# REVB.net
KiCad netlist of a schematic drawn in EAGLE
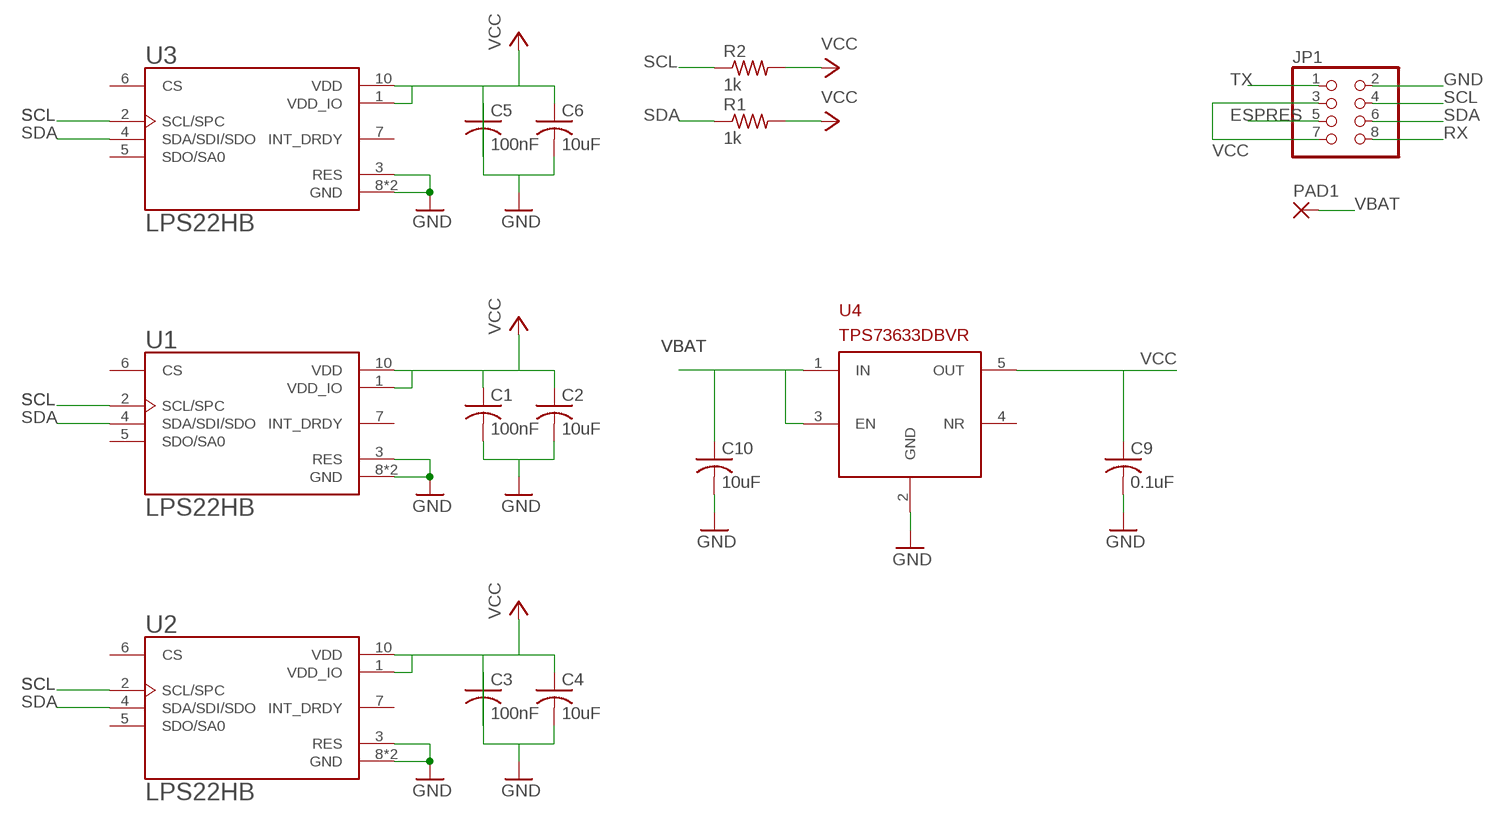
[diagram p0: schematic, sheet 1]

(export (version "E")
  (design (tool "Eeschema 10.0.6"))
  (components
    (comp (ref "C1")
      (value "100nF")
      (footprint "eagle-import:C0402")
      (libsource (lib "eagle-import") (part "C-USC0402"))
    )
    (comp (ref "C2")
      (value "10uF")
      (footprint "eagle-import:C0402")
      (libsource (lib "eagle-import") (part "C-USC0402"))
    )
    (comp (ref "C3")
      (value "100nF")
      (footprint "eagle-import:C0402")
      (libsource (lib "eagle-import") (part "C-USC0402"))
    )
    (comp (ref "C4")
      (value "10uF")
      (footprint "eagle-import:C0402")
      (libsource (lib "eagle-import") (part "C-USC0402"))
    )
    (comp (ref "C5")
      (value "100nF")
      (footprint "eagle-import:C0402")
      (libsource (lib "eagle-import") (part "C-USC0402"))
    )
    (comp (ref "C6")
      (value "10uF")
      (footprint "eagle-import:C0402")
      (libsource (lib "eagle-import") (part "C-USC0402"))
    )
    (comp (ref "C9")
      (value "0.1uF")
      (footprint "eagle-import:C0402")
      (libsource (lib "eagle-import") (part "C-USC0402"))
    )
    (comp (ref "C10")
      (value "10uF")
      (footprint "eagle-import:C0402")
      (libsource (lib "eagle-import") (part "C-USC0402"))
    )
    (comp (ref "JP1")
      (value "PINHD-2X4/90")
      (footprint "eagle-import:2X04_90")
      (libsource (lib "eagle-import") (part "PINHD-2X4/90"))
    )
    (comp (ref "PAD1")
      (value "2,15/1,0")
      (footprint "eagle-import:2,15_1,0")
      (libsource (lib "eagle-import") (part "2,15/1,0"))
    )
    (comp (ref "R1")
      (value "1k")
      (footprint "eagle-import:R0402")
      (libsource (lib "eagle-import") (part "R-US_R0402"))
    )
    (comp (ref "R2")
      (value "1k")
      (footprint "eagle-import:R0402")
      (libsource (lib "eagle-import") (part "R-US_R0402"))
    )
    (comp (ref "U1")
      (value "LPS22HB")
      (footprint "eagle-import:LGA10R50P2X3_200X200X80")
      (fields (field (name "MF") "STMicroelectronics"))
      (libsource (lib "eagle-import") (part "LPS22HB"))
    )
    (comp (ref "U2")
      (value "LPS22HB")
      (footprint "eagle-import:LGA10R50P2X3_200X200X80")
      (fields (field (name "MF") "STMicroelectronics"))
      (libsource (lib "eagle-import") (part "LPS22HB"))
    )
    (comp (ref "U3")
      (value "LPS22HB")
      (footprint "eagle-import:LGA10R50P2X3_200X200X80")
      (fields (field (name "MF") "STMicroelectronics"))
      (libsource (lib "eagle-import") (part "LPS22HB"))
    )
    (comp (ref "U4")
      (value "TPS73633DBVR")
      (footprint "eagle-import:SOT23-DBV")
      (fields (field (name "MF") "Texas Instruments"))
      (libsource (lib "eagle-import") (part "TPS73633DBVR"))
    )
  )
  (nets
    (net (code "1") (name "/ESPRES") (class "Default")
      (node (ref "JP1") (pin "5") (pinfunction "5_5") (pintype "passive"))
    )
    (net (code "2") (name "/RX") (class "Default")
      (node (ref "JP1") (pin "8") (pinfunction "8_8") (pintype "passive"))
    )
    (net (code "3") (name "/SCL") (class "Default")
      (node (ref "JP1") (pin "4") (pinfunction "4_4") (pintype "passive"))
      (node (ref "R2") (pin "1") (pinfunction "1_1") (pintype "passive"))
      (node (ref "U1") (pin "2") (pinfunction "SCL/SPC_2") (pintype "input"))
      (node (ref "U2") (pin "2") (pinfunction "SCL/SPC_2") (pintype "input"))
      (node (ref "U3") (pin "2") (pinfunction "SCL/SPC_2") (pintype "input"))
    )
    (net (code "4") (name "/SDA") (class "Default")
      (node (ref "JP1") (pin "6") (pinfunction "6_6") (pintype "passive"))
      (node (ref "R1") (pin "1") (pinfunction "1_1") (pintype "passive"))
      (node (ref "U1") (pin "4") (pinfunction "SDA/SDI/SDO_4") (pintype "bidirectional"))
      (node (ref "U2") (pin "4") (pinfunction "SDA/SDI/SDO_4") (pintype "bidirectional"))
      (node (ref "U3") (pin "4") (pinfunction "SDA/SDI/SDO_4") (pintype "bidirectional"))
    )
    (net (code "5") (name "/TX") (class "Default")
      (node (ref "JP1") (pin "1") (pinfunction "1_1") (pintype "passive"))
    )
    (net (code "6") (name "/VBAT") (class "Default")
      (node (ref "C10") (pin "1") (pinfunction "1_1") (pintype "passive"))
      (node (ref "PAD1") (pin "1") (pinfunction "P_1") (pintype "passive"))
      (node (ref "U4") (pin "1") (pinfunction "IN_1") (pintype "bidirectional"))
      (node (ref "U4") (pin "3") (pinfunction "EN_3") (pintype "bidirectional"))
    )
    (net (code "7") (name "GND") (class "Default")
      (node (ref "C1") (pin "2") (pinfunction "2_2") (pintype "passive"))
      (node (ref "C10") (pin "2") (pinfunction "2_2") (pintype "passive"))
      (node (ref "C2") (pin "2") (pinfunction "2_2") (pintype "passive"))
      (node (ref "C3") (pin "1") (pinfunction "1_1") (pintype "passive"))
      (node (ref "C4") (pin "2") (pinfunction "2_2") (pintype "passive"))
      (node (ref "C5") (pin "1") (pinfunction "1_1") (pintype "passive"))
      (node (ref "C6") (pin "2") (pinfunction "2_2") (pintype "passive"))
      (node (ref "C9") (pin "2") (pinfunction "2_2") (pintype "passive"))
      (node (ref "JP1") (pin "2") (pinfunction "2_2") (pintype "passive"))
      (node (ref "U1") (pin "3") (pinfunction "RES_3") (pintype "power_in"))
      (node (ref "U1") (pin "8") (pinfunction "GND_8") (pintype "power_in"))
      (node (ref "U1") (pin "9") (pinfunction "GND_9") (pintype "power_in"))
      (node (ref "U2") (pin "3") (pinfunction "RES_3") (pintype "power_in"))
      (node (ref "U2") (pin "8") (pinfunction "GND_8") (pintype "power_in"))
      (node (ref "U2") (pin "9") (pinfunction "GND_9") (pintype "power_in"))
      (node (ref "U3") (pin "3") (pinfunction "RES_3") (pintype "power_in"))
      (node (ref "U3") (pin "8") (pinfunction "GND_8") (pintype "power_in"))
      (node (ref "U3") (pin "9") (pinfunction "GND_9") (pintype "power_in"))
      (node (ref "U4") (pin "2") (pinfunction "GND_2") (pintype "bidirectional"))
    )
    (net (code "8") (name "VCC") (class "Default")
      (node (ref "C1") (pin "1") (pinfunction "1_1") (pintype "passive"))
      (node (ref "C2") (pin "1") (pinfunction "1_1") (pintype "passive"))
      (node (ref "C3") (pin "2") (pinfunction "2_2") (pintype "passive"))
      (node (ref "C4") (pin "1") (pinfunction "1_1") (pintype "passive"))
      (node (ref "C5") (pin "2") (pinfunction "2_2") (pintype "passive"))
      (node (ref "C6") (pin "1") (pinfunction "1_1") (pintype "passive"))
      (node (ref "C9") (pin "1") (pinfunction "1_1") (pintype "passive"))
      (node (ref "JP1") (pin "3") (pinfunction "3_3") (pintype "passive"))
      (node (ref "JP1") (pin "7") (pinfunction "7_7") (pintype "passive"))
      (node (ref "R1") (pin "2") (pinfunction "2_2") (pintype "passive"))
      (node (ref "R2") (pin "2") (pinfunction "2_2") (pintype "passive"))
      (node (ref "U1") (pin "1") (pinfunction "VDD_IO_1") (pintype "power_in"))
      (node (ref "U1") (pin "10") (pinfunction "VDD_10") (pintype "power_in"))
      (node (ref "U2") (pin "1") (pinfunction "VDD_IO_1") (pintype "power_in"))
      (node (ref "U2") (pin "10") (pinfunction "VDD_10") (pintype "power_in"))
      (node (ref "U3") (pin "1") (pinfunction "VDD_IO_1") (pintype "power_in"))
      (node (ref "U3") (pin "10") (pinfunction "VDD_10") (pintype "power_in"))
      (node (ref "U4") (pin "5") (pinfunction "OUT_5") (pintype "bidirectional"))
    )
    (net (code "9") (name "unconnected-(U1-CS-Pad6)") (class "Default")
      (node (ref "U1") (pin "6") (pinfunction "CS_6") (pintype "input"))
    )
    (net (code "10") (name "unconnected-(U1-INT_DRDY-Pad7)") (class "Default")
      (node (ref "U1") (pin "7") (pinfunction "INT_DRDY_7") (pintype "output"))
    )
    (net (code "11") (name "unconnected-(U1-SDO{slash}SA0-Pad5)") (class "Default")
      (node (ref "U1") (pin "5") (pinfunction "SDO/SA0_5") (pintype "bidirectional"))
    )
    (net (code "12") (name "unconnected-(U2-CS-Pad6)") (class "Default")
      (node (ref "U2") (pin "6") (pinfunction "CS_6") (pintype "input"))
    )
    (net (code "13") (name "unconnected-(U2-INT_DRDY-Pad7)") (class "Default")
      (node (ref "U2") (pin "7") (pinfunction "INT_DRDY_7") (pintype "output"))
    )
    (net (code "14") (name "unconnected-(U2-SDO{slash}SA0-Pad5)") (class "Default")
      (node (ref "U2") (pin "5") (pinfunction "SDO/SA0_5") (pintype "bidirectional"))
    )
    (net (code "15") (name "unconnected-(U3-CS-Pad6)") (class "Default")
      (node (ref "U3") (pin "6") (pinfunction "CS_6") (pintype "input"))
    )
    (net (code "16") (name "unconnected-(U3-INT_DRDY-Pad7)") (class "Default")
      (node (ref "U3") (pin "7") (pinfunction "INT_DRDY_7") (pintype "output"))
    )
    (net (code "17") (name "unconnected-(U3-SDO{slash}SA0-Pad5)") (class "Default")
      (node (ref "U3") (pin "5") (pinfunction "SDO/SA0_5") (pintype "bidirectional"))
    )
    (net (code "18") (name "unconnected-(U4-NR-Pad4)") (class "Default")
      (node (ref "U4") (pin "4") (pinfunction "NR_4") (pintype "bidirectional"))
    )
  )
)
